# SERV.net
KiCad netlist of a schematic drawn in EAGLE
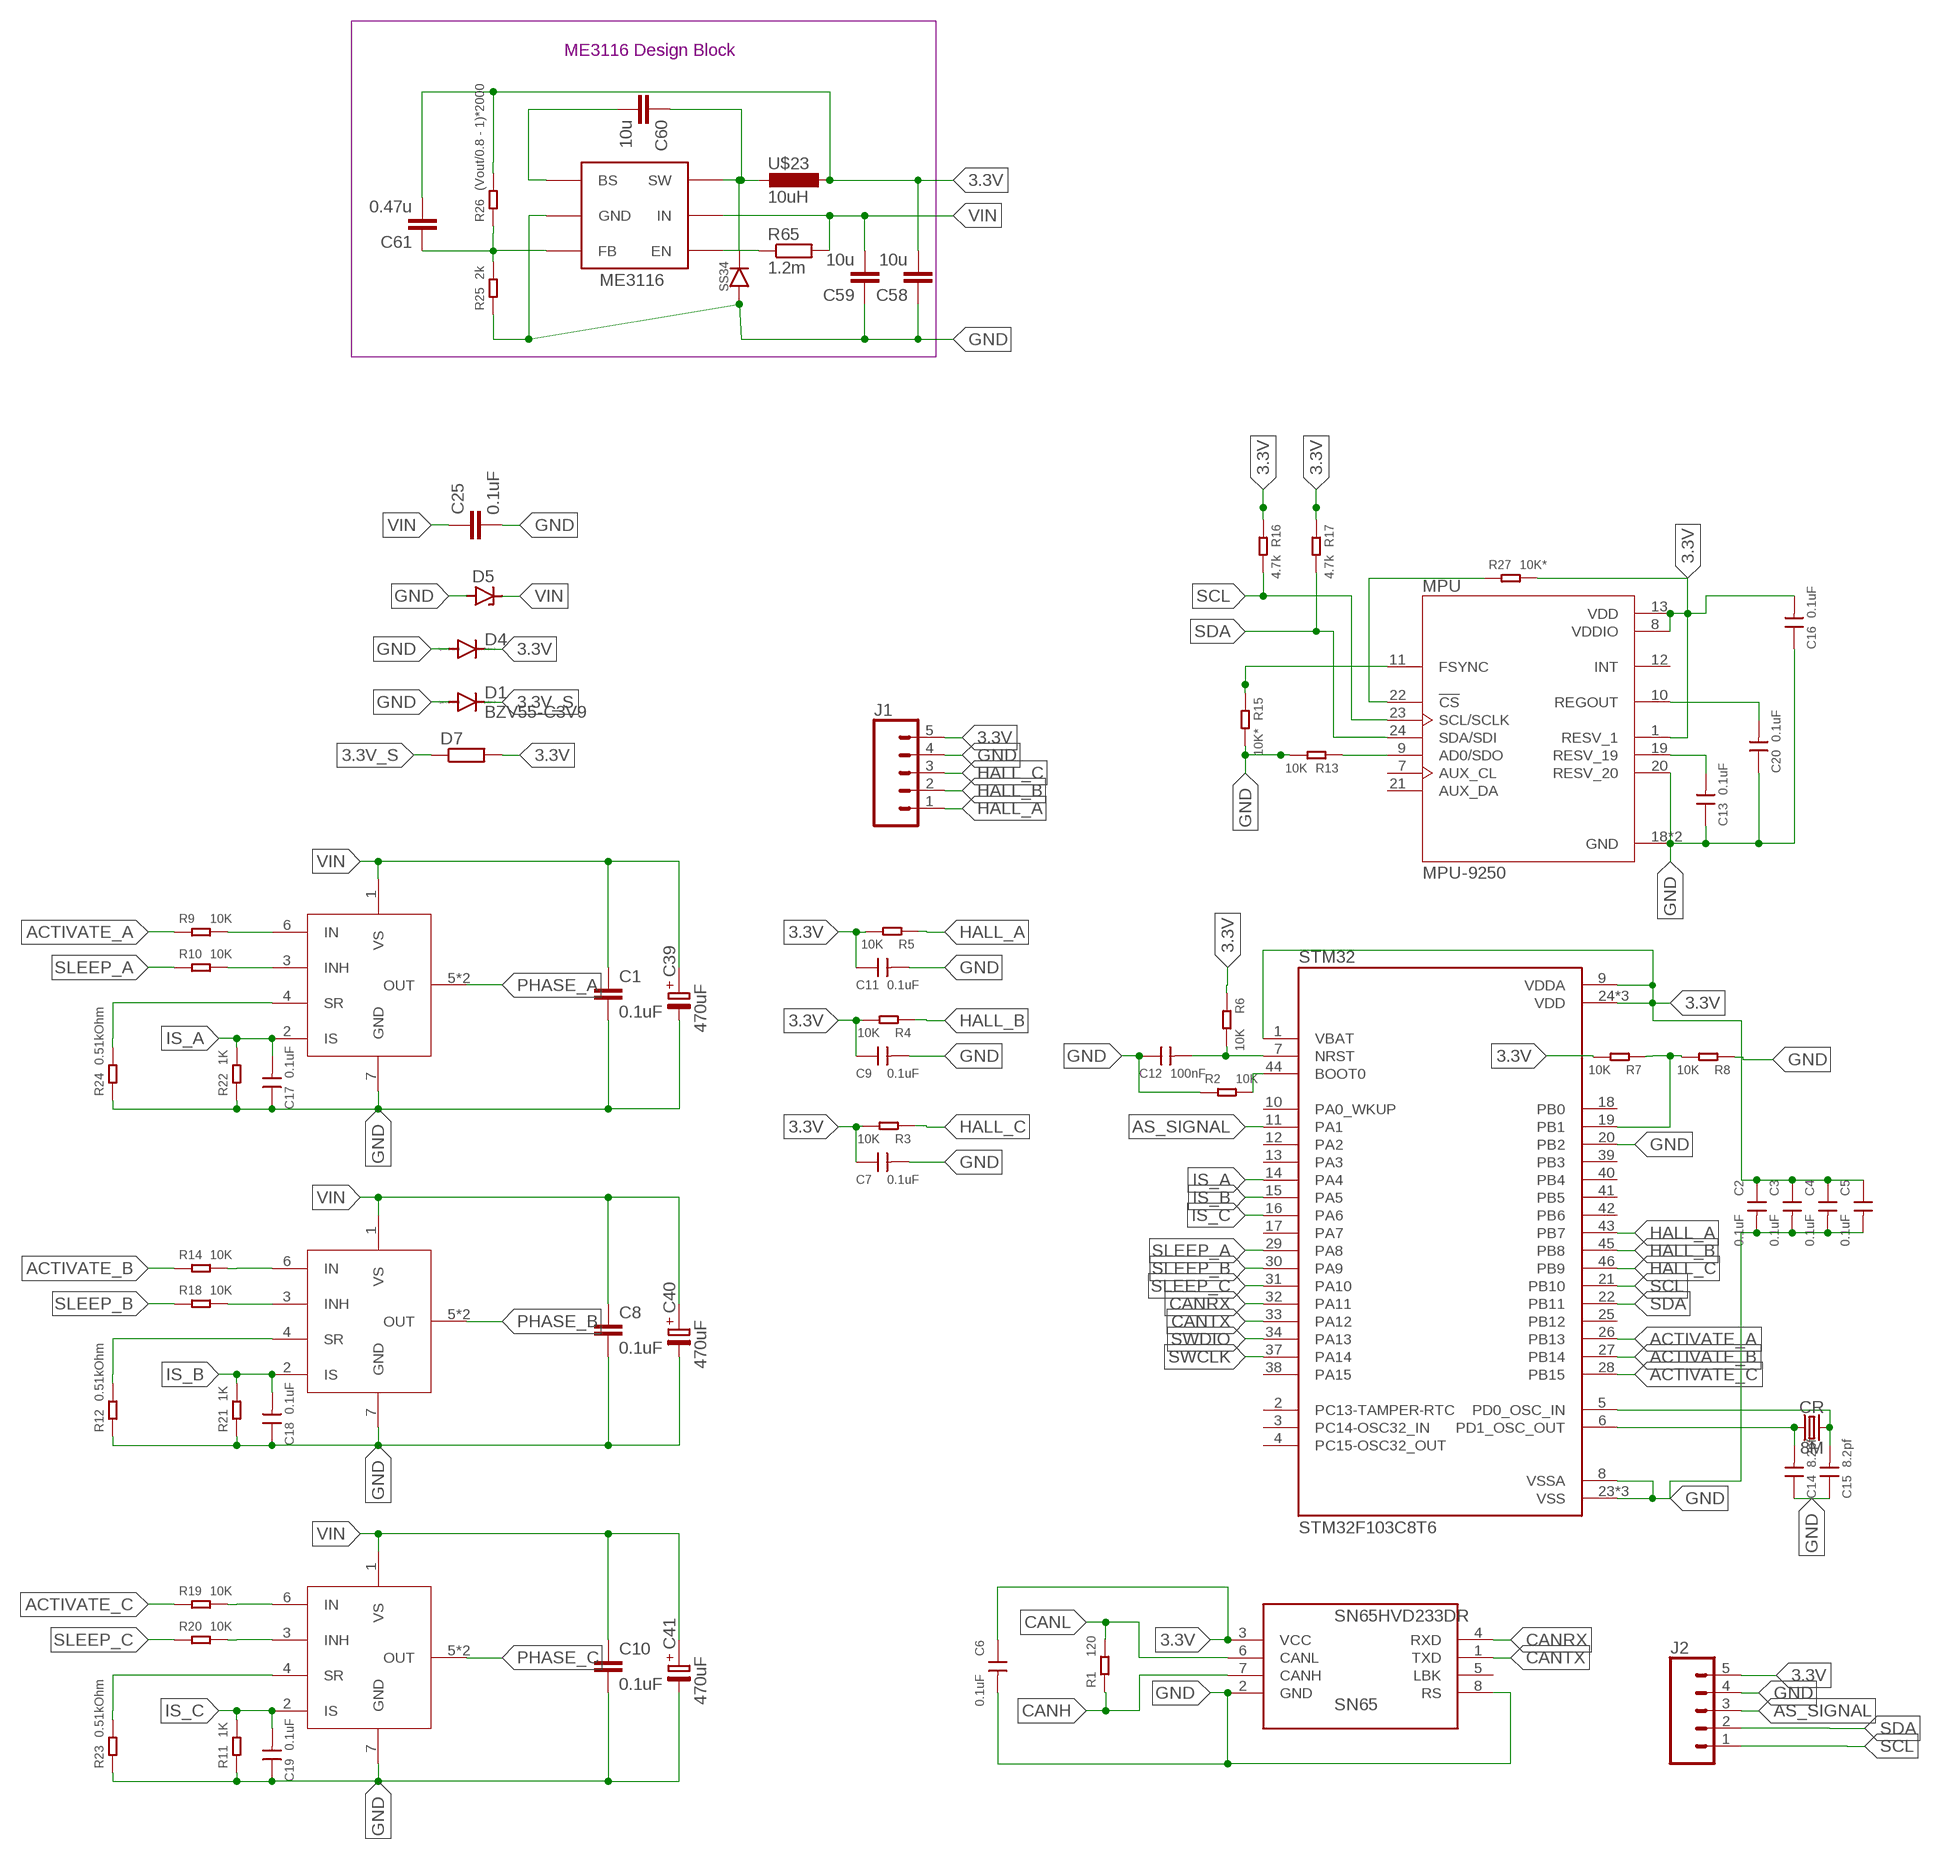
[diagram p0: schematic, sheet 1]

(export (version "E")
  (design (tool "Eeschema 10.0.6"))
  (components
    (comp (ref "BTN_A")
      (value "BTN7960B")
      (footprint "eagle-import:DPAK127P1500X440-8N")
      (libsource (lib "eagle-import") (part "BTN7960B"))
    )
    (comp (ref "BTN_B")
      (value "BTN7960B")
      (footprint "eagle-import:DPAK127P1500X440-8N")
      (libsource (lib "eagle-import") (part "BTN7960B"))
    )
    (comp (ref "BTN_C")
      (value "BTN7960B")
      (footprint "eagle-import:DPAK127P1500X440-8N")
      (libsource (lib "eagle-import") (part "BTN7960B"))
    )
    (comp (ref "C1")
      (value "0.1uF")
      (footprint "eagle-import:C1206")
      (libsource (lib "eagle-import") (part "C-EUC1206"))
    )
    (comp (ref "C2")
      (value "0.1uF")
      (footprint "eagle-import:0603")
      (libsource (lib "eagle-import") (part "C-0603"))
    )
    (comp (ref "C3")
      (value "0.1uF")
      (footprint "eagle-import:0603")
      (libsource (lib "eagle-import") (part "C-0603"))
    )
    (comp (ref "C4")
      (value "0.1uF")
      (footprint "eagle-import:0603")
      (libsource (lib "eagle-import") (part "C-0603"))
    )
    (comp (ref "C5")
      (value "0.1uF")
      (footprint "eagle-import:0603")
      (libsource (lib "eagle-import") (part "C-0603"))
    )
    (comp (ref "C6")
      (value "0.1uF")
      (footprint "eagle-import:0603")
      (libsource (lib "eagle-import") (part "C-0603"))
    )
    (comp (ref "C7")
      (value "0.1uF")
      (footprint "eagle-import:0603")
      (libsource (lib "eagle-import") (part "C-0603"))
    )
    (comp (ref "C8")
      (value "0.1uF")
      (footprint "eagle-import:C1206")
      (libsource (lib "eagle-import") (part "C-EUC1206"))
    )
    (comp (ref "C9")
      (value "0.1uF")
      (footprint "eagle-import:0603")
      (libsource (lib "eagle-import") (part "C-0603"))
    )
    (comp (ref "C10")
      (value "0.1uF")
      (footprint "eagle-import:C1206")
      (libsource (lib "eagle-import") (part "C-EUC1206"))
    )
    (comp (ref "C11")
      (value "0.1uF")
      (footprint "eagle-import:0603")
      (libsource (lib "eagle-import") (part "C-0603"))
    )
    (comp (ref "C12")
      (value "100nF")
      (footprint "eagle-import:0603")
      (libsource (lib "eagle-import") (part "C-0603"))
    )
    (comp (ref "C13")
      (value "0.1uF")
      (footprint "eagle-import:0603")
      (libsource (lib "eagle-import") (part "C-0603"))
    )
    (comp (ref "C14")
      (value "8.2pf")
      (footprint "eagle-import:0603")
      (libsource (lib "eagle-import") (part "C-0603"))
    )
    (comp (ref "C15")
      (value "8.2pf")
      (footprint "eagle-import:0603")
      (libsource (lib "eagle-import") (part "C-0603"))
    )
    (comp (ref "C16")
      (value "0.1uF")
      (footprint "eagle-import:0603")
      (libsource (lib "eagle-import") (part "C-0603"))
    )
    (comp (ref "C17")
      (value "0.1uF")
      (footprint "eagle-import:0603")
      (libsource (lib "eagle-import") (part "C-0603"))
    )
    (comp (ref "C18")
      (value "0.1uF")
      (footprint "eagle-import:0603")
      (libsource (lib "eagle-import") (part "C-0603"))
    )
    (comp (ref "C19")
      (value "0.1uF")
      (footprint "eagle-import:0603")
      (libsource (lib "eagle-import") (part "C-0603"))
    )
    (comp (ref "C20")
      (value "0.1uF")
      (footprint "eagle-import:0603")
      (libsource (lib "eagle-import") (part "C-0603"))
    )
    (comp (ref "C25")
      (value "0.1uF")
      (footprint "eagle-import:C1206")
      (libsource (lib "eagle-import") (part "C-EUC1206"))
    )
    (comp (ref "C39")
      (value "470uF")
      (footprint "eagle-import:TE-D-7343")
      (libsource (lib "eagle-import") (part "C-PR-SMD-TE-D"))
    )
    (comp (ref "C40")
      (value "470uF")
      (footprint "eagle-import:TE-D-7343")
      (libsource (lib "eagle-import") (part "C-PR-SMD-TE-D"))
    )
    (comp (ref "C41")
      (value "470uF")
      (footprint "eagle-import:TE-D-7343")
      (libsource (lib "eagle-import") (part "C-PR-SMD-TE-D"))
    )
    (comp (ref "C58")
      (value "10u")
      (footprint "eagle-import:C0805")
      (libsource (lib "eagle-import") (part "C-EUC0805"))
    )
    (comp (ref "C59")
      (value "10u")
      (footprint "eagle-import:C0805")
      (libsource (lib "eagle-import") (part "C-EUC0805"))
    )
    (comp (ref "C60")
      (value "10u")
      (footprint "eagle-import:C0805")
      (libsource (lib "eagle-import") (part "C-EUC0805"))
    )
    (comp (ref "C61")
      (value "0.47u")
      (footprint "eagle-import:C0805")
      (libsource (lib "eagle-import") (part "C-EUC0805"))
    )
    (comp (ref "CR")
      (value "8M")
      (footprint "eagle-import:CRYSTAL-SMD-3.2X2.5MM")
      (libsource (lib "eagle-import") (part "CRYSTALSMD-3.2X2.5"))
    )
    (comp (ref "D1")
      (value "BZV55-C3V9")
      (footprint "eagle-import:MINIMELF")
      (libsource (lib "eagle-import") (part "DIODE-MINIMELF"))
    )
    (comp (ref "D4")
      (value "DIODE-MINIMELF")
      (footprint "eagle-import:MINIMELF")
      (libsource (lib "eagle-import") (part "DIODE-MINIMELF"))
    )
    (comp (ref "D5")
      (value "ZENER-DIODESMB")
      (footprint "eagle-import:SMB")
      (libsource (lib "eagle-import") (part "ZENER-DIODESMB"))
    )
    (comp (ref "D7")
      (value "R-EU_R0805W")
      (footprint "eagle-import:R0805W")
      (libsource (lib "eagle-import") (part "R-EU_R0805W"))
    )
    (comp (ref "J1")
      (value "CONN_05")
      (footprint "eagle-import:1X05")
      (libsource (lib "eagle-import") (part "CONN_05"))
    )
    (comp (ref "J2")
      (value "CONN_05")
      (footprint "eagle-import:1X05")
      (libsource (lib "eagle-import") (part "CONN_05"))
    )
    (comp (ref "ME311")
      (value "ME3116")
      (footprint "eagle-import:SOT-23-6")
      (libsource (lib "eagle-import") (part "ME3116"))
    )
    (comp (ref "MPU")
      (value "MPU-9250")
      (footprint "eagle-import:QFN40P300X300X105-24N")
      (fields (field (name "MF") "TDK InvenSense"))
      (libsource (lib "eagle-import") (part "MPU-9250"))
    )
    (comp (ref "R1")
      (value "120")
      (footprint "eagle-import:0603")
      (libsource (lib "eagle-import") (part "R-0603"))
    )
    (comp (ref "R2")
      (value "10K")
      (footprint "eagle-import:0603")
      (libsource (lib "eagle-import") (part "R-0603"))
    )
    (comp (ref "R3")
      (value "10K")
      (footprint "eagle-import:0603")
      (libsource (lib "eagle-import") (part "R-0603"))
    )
    (comp (ref "R4")
      (value "10K")
      (footprint "eagle-import:0603")
      (libsource (lib "eagle-import") (part "R-0603"))
    )
    (comp (ref "R5")
      (value "10K")
      (footprint "eagle-import:0603")
      (libsource (lib "eagle-import") (part "R-0603"))
    )
    (comp (ref "R6")
      (value "10K")
      (footprint "eagle-import:0603")
      (libsource (lib "eagle-import") (part "R-0603"))
    )
    (comp (ref "R7")
      (value "10K")
      (footprint "eagle-import:0603")
      (libsource (lib "eagle-import") (part "R-0603"))
    )
    (comp (ref "R8")
      (value "10K")
      (footprint "eagle-import:0603")
      (libsource (lib "eagle-import") (part "R-0603"))
    )
    (comp (ref "R9")
      (value "10K")
      (footprint "eagle-import:0603")
      (libsource (lib "eagle-import") (part "R-0603"))
    )
    (comp (ref "R10")
      (value "10K")
      (footprint "eagle-import:0603")
      (libsource (lib "eagle-import") (part "R-0603"))
    )
    (comp (ref "R11")
      (value "1K")
      (footprint "eagle-import:0603")
      (libsource (lib "eagle-import") (part "R-0603"))
    )
    (comp (ref "R12")
      (value "0.51kOhm")
      (footprint "eagle-import:0603")
      (libsource (lib "eagle-import") (part "R-0603"))
    )
    (comp (ref "R13")
      (value "10K")
      (footprint "eagle-import:0603")
      (libsource (lib "eagle-import") (part "R-0603"))
    )
    (comp (ref "R14")
      (value "10K")
      (footprint "eagle-import:0603")
      (libsource (lib "eagle-import") (part "R-0603"))
    )
    (comp (ref "R15")
      (value "10K*")
      (footprint "eagle-import:0603")
      (libsource (lib "eagle-import") (part "R-0603"))
    )
    (comp (ref "R16")
      (value "4.7k")
      (footprint "eagle-import:0603")
      (libsource (lib "eagle-import") (part "R-0603"))
    )
    (comp (ref "R17")
      (value "4.7k")
      (footprint "eagle-import:0603")
      (libsource (lib "eagle-import") (part "R-0603"))
    )
    (comp (ref "R18")
      (value "10K")
      (footprint "eagle-import:0603")
      (libsource (lib "eagle-import") (part "R-0603"))
    )
    (comp (ref "R19")
      (value "10K")
      (footprint "eagle-import:0603")
      (libsource (lib "eagle-import") (part "R-0603"))
    )
    (comp (ref "R20")
      (value "10K")
      (footprint "eagle-import:0603")
      (libsource (lib "eagle-import") (part "R-0603"))
    )
    (comp (ref "R21")
      (value "1K")
      (footprint "eagle-import:0603")
      (libsource (lib "eagle-import") (part "R-0603"))
    )
    (comp (ref "R22")
      (value "1K")
      (footprint "eagle-import:0603")
      (libsource (lib "eagle-import") (part "R-0603"))
    )
    (comp (ref "R23")
      (value "0.51kOhm")
      (footprint "eagle-import:0603")
      (libsource (lib "eagle-import") (part "R-0603"))
    )
    (comp (ref "R24")
      (value "0.51kOhm")
      (footprint "eagle-import:0603")
      (libsource (lib "eagle-import") (part "R-0603"))
    )
    (comp (ref "R25")
      (value "2k")
      (footprint "eagle-import:0603")
      (libsource (lib "eagle-import") (part "R-0603"))
    )
    (comp (ref "R26")
      (value "(Vout/0.8 - 1)*2000")
      (footprint "eagle-import:0603")
      (libsource (lib "eagle-import") (part "R-0603"))
    )
    (comp (ref "R27")
      (value "10K*")
      (footprint "eagle-import:0603")
      (libsource (lib "eagle-import") (part "R-0603"))
    )
    (comp (ref "R65")
      (value "1.2m")
      (footprint "eagle-import:R0603")
      (libsource (lib "eagle-import") (part "R-EU_R0603"))
    )
    (comp (ref "SN65")
      (value "SN65HVD233DR")
      (footprint "eagle-import:SOIC8")
      (fields (field (name "MF") "Texas Instruments"))
      (libsource (lib "eagle-import") (part "SN65HVD233DR"))
    )
    (comp (ref "STM32")
      (value "STM32F103C8T6")
      (footprint "eagle-import:QFP50P900X900X160-48N")
      (fields (field (name "MF") "STMicroelectronics"))
      (libsource (lib "eagle-import") (part "STM32F103C8T6"))
    )
    (comp (ref "U$1")
      (value "SMA-SS34")
      (footprint "eagle-import:SMA-SS34")
      (libsource (lib "eagle-import") (part "SMA-SS34"))
    )
    (comp (ref "U$23")
      (value "10uH")
      (footprint "eagle-import:CD43")
      (libsource (lib "eagle-import") (part "INDUCTOR_CD43"))
    )
  )
  (nets
    (net (code "1") (name "3.3V") (class "Default")
      (node (ref "C11") (pin "1") (pinfunction "1_1") (pintype "passive"))
      (node (ref "C16") (pin "2") (pinfunction "2_2") (pintype "passive"))
      (node (ref "C2") (pin "1") (pinfunction "1_1") (pintype "passive"))
      (node (ref "C3") (pin "1") (pinfunction "1_1") (pintype "passive"))
      (node (ref "C4") (pin "1") (pinfunction "1_1") (pintype "passive"))
      (node (ref "C5") (pin "1") (pinfunction "1_1") (pintype "passive"))
      (node (ref "C58") (pin "2") (pinfunction "2_2") (pintype "passive"))
      (node (ref "C6") (pin "1") (pinfunction "1_1") (pintype "passive"))
      (node (ref "C61") (pin "2") (pinfunction "2_2") (pintype "passive"))
      (node (ref "C7") (pin "1") (pinfunction "1_1") (pintype "passive"))
      (node (ref "C9") (pin "1") (pinfunction "1_1") (pintype "passive"))
      (node (ref "D4") (pin "C") (pinfunction "C_C") (pintype "passive"))
      (node (ref "D7") (pin "2") (pinfunction "2_2") (pintype "passive"))
      (node (ref "J1") (pin "5") (pinfunction "5_5") (pintype "passive"))
      (node (ref "J2") (pin "5") (pinfunction "5_5") (pintype "passive"))
      (node (ref "MPU") (pin "1") (pinfunction "RESV_1_1") (pintype "passive"))
      (node (ref "MPU") (pin "13") (pinfunction "VDD_13") (pintype "power_in"))
      (node (ref "MPU") (pin "8") (pinfunction "VDDIO_8") (pintype "power_in"))
      (node (ref "R16") (pin "1") (pinfunction "1_1") (pintype "passive"))
      (node (ref "R17") (pin "1") (pinfunction "1_1") (pintype "passive"))
      (node (ref "R26") (pin "2") (pinfunction "2_2") (pintype "passive"))
      (node (ref "R27") (pin "2") (pinfunction "2_2") (pintype "passive"))
      (node (ref "R3") (pin "2") (pinfunction "2_2") (pintype "passive"))
      (node (ref "R4") (pin "2") (pinfunction "2_2") (pintype "passive"))
      (node (ref "R5") (pin "2") (pinfunction "2_2") (pintype "passive"))
      (node (ref "R6") (pin "1") (pinfunction "1_1") (pintype "passive"))
      (node (ref "R7") (pin "2") (pinfunction "2_2") (pintype "passive"))
      (node (ref "SN65") (pin "3") (pinfunction "VCC_3") (pintype "power_in"))
      (node (ref "STM32") (pin "1") (pinfunction "VBAT_1") (pintype "bidirectional"))
      (node (ref "STM32") (pin "24") (pinfunction "VDD_24") (pintype "power_in"))
      (node (ref "STM32") (pin "36") (pinfunction "VDD_36") (pintype "power_in"))
      (node (ref "STM32") (pin "48") (pinfunction "VDD_48") (pintype "power_in"))
      (node (ref "STM32") (pin "9") (pinfunction "VDDA_9") (pintype "power_in"))
      (node (ref "U$23") (pin "P$1") (pinfunction "1_P$1") (pintype "passive"))
    )
    (net (code "2") (name "3.3V_S") (class "Default")
      (node (ref "D1") (pin "C") (pinfunction "C_C") (pintype "passive"))
      (node (ref "D7") (pin "1") (pinfunction "1_1") (pintype "passive"))
    )
    (net (code "3") (name "ACTIVATE_A") (class "Default")
      (node (ref "R9") (pin "1") (pinfunction "1_1") (pintype "passive"))
      (node (ref "STM32") (pin "26") (pinfunction "PB13_26") (pintype "bidirectional"))
    )
    (net (code "4") (name "ACTIVATE_B") (class "Default")
      (node (ref "R14") (pin "1") (pinfunction "1_1") (pintype "passive"))
      (node (ref "STM32") (pin "27") (pinfunction "PB14_27") (pintype "bidirectional"))
    )
    (net (code "5") (name "ACTIVATE_C") (class "Default")
      (node (ref "R19") (pin "1") (pinfunction "1_1") (pintype "passive"))
      (node (ref "STM32") (pin "28") (pinfunction "PB15_28") (pintype "bidirectional"))
    )
    (net (code "6") (name "AS_SIGNAL") (class "Default")
      (node (ref "J2") (pin "3") (pinfunction "3_3") (pintype "passive"))
      (node (ref "STM32") (pin "11") (pinfunction "PA1_11") (pintype "bidirectional"))
    )
    (net (code "7") (name "CANH") (class "Default")
      (node (ref "R1") (pin "1") (pinfunction "1_1") (pintype "passive"))
      (node (ref "SN65") (pin "7") (pinfunction "CANH_7") (pintype "bidirectional"))
    )
    (net (code "8") (name "CANL") (class "Default")
      (node (ref "R1") (pin "2") (pinfunction "2_2") (pintype "passive"))
      (node (ref "SN65") (pin "6") (pinfunction "CANL_6") (pintype "bidirectional"))
    )
    (net (code "9") (name "CANRX") (class "Default")
      (node (ref "SN65") (pin "4") (pinfunction "RXD_4") (pintype "output"))
      (node (ref "STM32") (pin "32") (pinfunction "PA11_32") (pintype "bidirectional"))
    )
    (net (code "10") (name "CANTX") (class "Default")
      (node (ref "SN65") (pin "1") (pinfunction "TXD_1") (pintype "bidirectional"))
      (node (ref "STM32") (pin "33") (pinfunction "PA12_33") (pintype "bidirectional"))
    )
    (net (code "11") (name "GND") (class "Default")
      (node (ref "BTN_A") (pin "7") (pinfunction "GND_7") (pintype "bidirectional"))
      (node (ref "BTN_B") (pin "7") (pinfunction "GND_7") (pintype "bidirectional"))
      (node (ref "BTN_C") (pin "7") (pinfunction "GND_7") (pintype "bidirectional"))
      (node (ref "C1") (pin "2") (pinfunction "2_2") (pintype "passive"))
      (node (ref "C10") (pin "2") (pinfunction "2_2") (pintype "passive"))
      (node (ref "C11") (pin "2") (pinfunction "2_2") (pintype "passive"))
      (node (ref "C12") (pin "1") (pinfunction "1_1") (pintype "passive"))
      (node (ref "C13") (pin "1") (pinfunction "1_1") (pintype "passive"))
      (node (ref "C14") (pin "1") (pinfunction "1_1") (pintype "passive"))
      (node (ref "C15") (pin "1") (pinfunction "1_1") (pintype "passive"))
      (node (ref "C16") (pin "1") (pinfunction "1_1") (pintype "passive"))
      (node (ref "C17") (pin "1") (pinfunction "1_1") (pintype "passive"))
      (node (ref "C18") (pin "1") (pinfunction "1_1") (pintype "passive"))
      (node (ref "C19") (pin "1") (pinfunction "1_1") (pintype "passive"))
      (node (ref "C2") (pin "2") (pinfunction "2_2") (pintype "passive"))
      (node (ref "C20") (pin "1") (pinfunction "1_1") (pintype "passive"))
      (node (ref "C25") (pin "2") (pinfunction "2_2") (pintype "passive"))
      (node (ref "C3") (pin "2") (pinfunction "2_2") (pintype "passive"))
      (node (ref "C39") (pin "-") (pinfunction "-_-") (pintype "passive"))
      (node (ref "C4") (pin "2") (pinfunction "2_2") (pintype "passive"))
      (node (ref "C40") (pin "-") (pinfunction "-_-") (pintype "passive"))
      (node (ref "C41") (pin "-") (pinfunction "-_-") (pintype "passive"))
      (node (ref "C5") (pin "2") (pinfunction "2_2") (pintype "passive"))
      (node (ref "C58") (pin "1") (pinfunction "1_1") (pintype "passive"))
      (node (ref "C59") (pin "1") (pinfunction "1_1") (pintype "passive"))
      (node (ref "C6") (pin "2") (pinfunction "2_2") (pintype "passive"))
      (node (ref "C7") (pin "2") (pinfunction "2_2") (pintype "passive"))
      (node (ref "C8") (pin "2") (pinfunction "2_2") (pintype "passive"))
      (node (ref "C9") (pin "2") (pinfunction "2_2") (pintype "passive"))
      (node (ref "D1") (pin "A") (pinfunction "A_A") (pintype "passive"))
      (node (ref "D4") (pin "A") (pinfunction "A_A") (pintype "passive"))
      (node (ref "D5") (pin "A") (pinfunction "A_A") (pintype "passive"))
      (node (ref "J1") (pin "4") (pinfunction "4_4") (pintype "passive"))
      (node (ref "J2") (pin "4") (pinfunction "4_4") (pintype "passive"))
      (node (ref "ME311") (pin "2") (pinfunction "GND_2") (pintype "bidirectional"))
      (node (ref "MPU") (pin "18") (pinfunction "GND_18") (pintype "power_in"))
      (node (ref "MPU") (pin "20") (pinfunction "RESV_20_20") (pintype "passive"))
      (node (ref "MPU") (pin "25") (pinfunction "GND_25") (pintype "power_in"))
      (node (ref "R11") (pin "1") (pinfunction "1_1") (pintype "passive"))
      (node (ref "R12") (pin "1") (pinfunction "1_1") (pintype "passive"))
      (node (ref "R13") (pin "2") (pinfunction "2_2") (pintype "passive"))
      (node (ref "R15") (pin "2") (pinfunction "2_2") (pintype "passive"))
      (node (ref "R2") (pin "1") (pinfunction "1_1") (pintype "passive"))
      (node (ref "R21") (pin "1") (pinfunction "1_1") (pintype "passive"))
      (node (ref "R22") (pin "1") (pinfunction "1_1") (pintype "passive"))
      (node (ref "R23") (pin "1") (pinfunction "1_1") (pintype "passive"))
      (node (ref "R24") (pin "1") (pinfunction "1_1") (pintype "passive"))
      (node (ref "R25") (pin "1") (pinfunction "1_1") (pintype "passive"))
      (node (ref "R8") (pin "1") (pinfunction "1_1") (pintype "passive"))
      (node (ref "SN65") (pin "2") (pinfunction "GND_2") (pintype "power_in"))
      (node (ref "SN65") (pin "8") (pinfunction "RS_8") (pintype "input"))
      (node (ref "STM32") (pin "20") (pinfunction "PB2_20") (pintype "bidirectional"))
      (node (ref "STM32") (pin "23") (pinfunction "VSS_23") (pintype "power_in"))
      (node (ref "STM32") (pin "35") (pinfunction "VSS_35") (pintype "power_in"))
      (node (ref "STM32") (pin "47") (pinfunction "VSS_47") (pintype "power_in"))
      (node (ref "STM32") (pin "8") (pinfunction "VSSA_8") (pintype "power_in"))
      (node (ref "U$1") (pin "1") (pinfunction "IN_1") (pintype "input"))
    )
    (net (code "12") (name "HALL_A") (class "Default")
      (node (ref "J1") (pin "1") (pinfunction "1_1") (pintype "passive"))
      (node (ref "R5") (pin "1") (pinfunction "1_1") (pintype "passive"))
      (node (ref "STM32") (pin "43") (pinfunction "PB7_43") (pintype "bidirectional"))
    )
    (net (code "13") (name "HALL_B") (class "Default")
      (node (ref "J1") (pin "2") (pinfunction "2_2") (pintype "passive"))
      (node (ref "R4") (pin "1") (pinfunction "1_1") (pintype "passive"))
      (node (ref "STM32") (pin "45") (pinfunction "PB8_45") (pintype "bidirectional"))
    )
    (net (code "14") (name "HALL_C") (class "Default")
      (node (ref "J1") (pin "3") (pinfunction "3_3") (pintype "passive"))
      (node (ref "R3") (pin "1") (pinfunction "1_1") (pintype "passive"))
      (node (ref "STM32") (pin "46") (pinfunction "PB9_46") (pintype "bidirectional"))
    )
    (net (code "15") (name "IS_A") (class "Default")
      (node (ref "BTN_C") (pin "2") (pinfunction "IS_2") (pintype "bidirectional"))
      (node (ref "C17") (pin "2") (pinfunction "2_2") (pintype "passive"))
      (node (ref "R22") (pin "2") (pinfunction "2_2") (pintype "passive"))
      (node (ref "STM32") (pin "14") (pinfunction "PA4_14") (pintype "bidirectional"))
    )
    (net (code "16") (name "IS_B") (class "Default")
      (node (ref "BTN_B") (pin "2") (pinfunction "IS_2") (pintype "bidirectional"))
      (node (ref "C18") (pin "2") (pinfunction "2_2") (pintype "passive"))
      (node (ref "R21") (pin "2") (pinfunction "2_2") (pintype "passive"))
      (node (ref "STM32") (pin "15") (pinfunction "PA5_15") (pintype "bidirectional"))
    )
    (net (code "17") (name "IS_C") (class "Default")
      (node (ref "BTN_A") (pin "2") (pinfunction "IS_2") (pintype "bidirectional"))
      (node (ref "C19") (pin "2") (pinfunction "2_2") (pintype "passive"))
      (node (ref "R11") (pin "2") (pinfunction "2_2") (pintype "passive"))
      (node (ref "STM32") (pin "16") (pinfunction "PA6_16") (pintype "bidirectional"))
    )
    (net (code "18") (name "Net-(BTN_A-IN)") (class "Default")
      (node (ref "BTN_A") (pin "6") (pinfunction "IN_6") (pintype "bidirectional"))
      (node (ref "R19") (pin "2") (pinfunction "2_2") (pintype "passive"))
    )
    (net (code "19") (name "Net-(BTN_A-INH)") (class "Default")
      (node (ref "BTN_A") (pin "3") (pinfunction "INH_3") (pintype "bidirectional"))
      (node (ref "R20") (pin "2") (pinfunction "2_2") (pintype "passive"))
    )
    (net (code "20") (name "Net-(BTN_A-SR)") (class "Default")
      (node (ref "BTN_A") (pin "4") (pinfunction "SR_4") (pintype "bidirectional"))
      (node (ref "R23") (pin "2") (pinfunction "2_2") (pintype "passive"))
    )
    (net (code "21") (name "Net-(BTN_B-IN)") (class "Default")
      (node (ref "BTN_B") (pin "6") (pinfunction "IN_6") (pintype "bidirectional"))
      (node (ref "R14") (pin "2") (pinfunction "2_2") (pintype "passive"))
    )
    (net (code "22") (name "Net-(BTN_B-INH)") (class "Default")
      (node (ref "BTN_B") (pin "3") (pinfunction "INH_3") (pintype "bidirectional"))
      (node (ref "R18") (pin "2") (pinfunction "2_2") (pintype "passive"))
    )
    (net (code "23") (name "Net-(BTN_B-SR)") (class "Default")
      (node (ref "BTN_B") (pin "4") (pinfunction "SR_4") (pintype "bidirectional"))
      (node (ref "R12") (pin "2") (pinfunction "2_2") (pintype "passive"))
    )
    (net (code "24") (name "Net-(BTN_C-IN)") (class "Default")
      (node (ref "BTN_C") (pin "6") (pinfunction "IN_6") (pintype "bidirectional"))
      (node (ref "R9") (pin "2") (pinfunction "2_2") (pintype "passive"))
    )
    (net (code "25") (name "Net-(BTN_C-INH)") (class "Default")
      (node (ref "BTN_C") (pin "3") (pinfunction "INH_3") (pintype "bidirectional"))
      (node (ref "R10") (pin "2") (pinfunction "2_2") (pintype "passive"))
    )
    (net (code "26") (name "Net-(BTN_C-SR)") (class "Default")
      (node (ref "BTN_C") (pin "4") (pinfunction "SR_4") (pintype "bidirectional"))
      (node (ref "R24") (pin "2") (pinfunction "2_2") (pintype "passive"))
    )
    (net (code "27") (name "Net-(CR-2)") (class "Default")
      (node (ref "C15") (pin "2") (pinfunction "2_2") (pintype "passive"))
      (node (ref "CR") (pin "3") (pinfunction "2_3") (pintype "passive"))
      (node (ref "STM32") (pin "5") (pinfunction "PD0_OSC_IN_5") (pintype "bidirectional"))
    )
    (net (code "28") (name "Net-(ME311-BS)") (class "Default")
      (node (ref "C60") (pin "2") (pinfunction "2_2") (pintype "passive"))
      (node (ref "ME311") (pin "1") (pinfunction "BS_1") (pintype "bidirectional"))
    )
    (net (code "29") (name "Net-(ME311-EN)") (class "Default")
      (node (ref "ME311") (pin "4") (pinfunction "EN_4") (pintype "bidirectional"))
      (node (ref "R65") (pin "1") (pinfunction "1_1") (pintype "passive"))
    )
    (net (code "30") (name "Net-(ME311-FB)") (class "Default")
      (node (ref "C61") (pin "1") (pinfunction "1_1") (pintype "passive"))
      (node (ref "ME311") (pin "3") (pinfunction "FB_3") (pintype "bidirectional"))
      (node (ref "R25") (pin "2") (pinfunction "2_2") (pintype "passive"))
      (node (ref "R26") (pin "1") (pinfunction "1_1") (pintype "passive"))
    )
    (net (code "31") (name "Net-(ME311-SW)") (class "Default")
      (node (ref "C60") (pin "1") (pinfunction "1_1") (pintype "passive"))
      (node (ref "ME311") (pin "6") (pinfunction "SW_6") (pintype "bidirectional"))
      (node (ref "U$1") (pin "2") (pinfunction "OUT_2") (pintype "bidirectional"))
      (node (ref "U$23") (pin "P$2") (pinfunction "2_P$2") (pintype "passive"))
    )
    (net (code "32") (name "Net-(MPU-AD0{slash}SDO)") (class "Default")
      (node (ref "MPU") (pin "9") (pinfunction "AD0/SDO_9") (pintype "output"))
      (node (ref "R13") (pin "1") (pinfunction "1_1") (pintype "passive"))
    )
    (net (code "33") (name "Net-(MPU-FSYNC)") (class "Default")
      (node (ref "MPU") (pin "11") (pinfunction "FSYNC_11") (pintype "input"))
      (node (ref "R15") (pin "1") (pinfunction "1_1") (pintype "passive"))
    )
    (net (code "34") (name "Net-(MPU-REGOUT)") (class "Default")
      (node (ref "C20") (pin "2") (pinfunction "2_2") (pintype "passive"))
      (node (ref "MPU") (pin "10") (pinfunction "REGOUT_10") (pintype "output"))
    )
    (net (code "35") (name "Net-(MPU-RESV_19)") (class "Default")
      (node (ref "C13") (pin "2") (pinfunction "2_2") (pintype "passive"))
      (node (ref "MPU") (pin "19") (pinfunction "RESV_19_19") (pintype "passive"))
    )
    (net (code "36") (name "Net-(MPU-~{CS})") (class "Default")
      (node (ref "MPU") (pin "22") (pinfunction "~{CS}_22") (pintype "input"))
      (node (ref "R27") (pin "1") (pinfunction "1_1") (pintype "passive"))
    )
    (net (code "37") (name "Net-(STM32-BOOT0)") (class "Default")
      (node (ref "R2") (pin "2") (pinfunction "2_2") (pintype "passive"))
      (node (ref "STM32") (pin "44") (pinfunction "BOOT0_44") (pintype "input"))
    )
    (net (code "38") (name "Net-(STM32-NRST)") (class "Default")
      (node (ref "C12") (pin "2") (pinfunction "2_2") (pintype "passive"))
      (node (ref "R6") (pin "2") (pinfunction "2_2") (pintype "passive"))
      (node (ref "STM32") (pin "7") (pinfunction "NRST_7") (pintype "input"))
    )
    (net (code "39") (name "Net-(STM32-PB1)") (class "Default")
      (node (ref "R7") (pin "1") (pinfunction "1_1") (pintype "passive"))
      (node (ref "R8") (pin "2") (pinfunction "2_2") (pintype "passive"))
      (node (ref "STM32") (pin "19") (pinfunction "PB1_19") (pintype "bidirectional"))
    )
    (net (code "40") (name "Net-(STM32-PD1_OSC_OUT)") (class "Default")
      (node (ref "C14") (pin "2") (pinfunction "2_2") (pintype "passive"))
      (node (ref "CR") (pin "1") (pinfunction "1_1") (pintype "passive"))
      (node (ref "STM32") (pin "6") (pinfunction "PD1_OSC_OUT_6") (pintype "bidirectional"))
    )
    (net (code "41") (name "PHASE_A") (class "Default")
      (node (ref "BTN_C") (pin "5") (pinfunction "OUT_5") (pintype "bidirectional"))
      (node (ref "BTN_C") (pin "8") (pinfunction "OUT_8") (pintype "bidirectional"))
    )
    (net (code "42") (name "PHASE_B") (class "Default")
      (node (ref "BTN_B") (pin "5") (pinfunction "OUT_5") (pintype "bidirectional"))
      (node (ref "BTN_B") (pin "8") (pinfunction "OUT_8") (pintype "bidirectional"))
    )
    (net (code "43") (name "PHASE_C") (class "Default")
      (node (ref "BTN_A") (pin "5") (pinfunction "OUT_5") (pintype "bidirectional"))
      (node (ref "BTN_A") (pin "8") (pinfunction "OUT_8") (pintype "bidirectional"))
    )
    (net (code "44") (name "SCL") (class "Default")
      (node (ref "J2") (pin "1") (pinfunction "1_1") (pintype "passive"))
      (node (ref "MPU") (pin "23") (pinfunction "SCL/SCLK_23") (pintype "input"))
      (node (ref "R16") (pin "2") (pinfunction "2_2") (pintype "passive"))
      (node (ref "STM32") (pin "21") (pinfunction "PB10_21") (pintype "bidirectional"))
    )
    (net (code "45") (name "SDA") (class "Default")
      (node (ref "J2") (pin "2") (pinfunction "2_2") (pintype "passive"))
      (node (ref "MPU") (pin "24") (pinfunction "SDA/SDI_24") (pintype "bidirectional"))
      (node (ref "R17") (pin "2") (pinfunction "2_2") (pintype "passive"))
      (node (ref "STM32") (pin "22") (pinfunction "PB11_22") (pintype "bidirectional"))
    )
    (net (code "46") (name "SLEEP_A") (class "Default")
      (node (ref "R10") (pin "1") (pinfunction "1_1") (pintype "passive"))
      (node (ref "STM32") (pin "29") (pinfunction "PA8_29") (pintype "bidirectional"))
    )
    (net (code "47") (name "SLEEP_B") (class "Default")
      (node (ref "R18") (pin "1") (pinfunction "1_1") (pintype "passive"))
      (node (ref "STM32") (pin "30") (pinfunction "PA9_30") (pintype "bidirectional"))
    )
    (net (code "48") (name "SLEEP_C") (class "Default")
      (node (ref "R20") (pin "1") (pinfunction "1_1") (pintype "passive"))
      (node (ref "STM32") (pin "31") (pinfunction "PA10_31") (pintype "bidirectional"))
    )
    (net (code "49") (name "SWCLK") (class "Default")
      (node (ref "STM32") (pin "37") (pinfunction "PA14_37") (pintype "bidirectional"))
    )
    (net (code "50") (name "SWDIO") (class "Default")
      (node (ref "STM32") (pin "34") (pinfunction "PA13_34") (pintype "bidirectional"))
    )
    (net (code "51") (name "VIN") (class "Default")
      (node (ref "BTN_A") (pin "1") (pinfunction "VS_1") (pintype "bidirectional"))
      (node (ref "BTN_B") (pin "1") (pinfunction "VS_1") (pintype "bidirectional"))
      (node (ref "BTN_C") (pin "1") (pinfunction "VS_1") (pintype "bidirectional"))
      (node (ref "C1") (pin "1") (pinfunction "1_1") (pintype "passive"))
      (node (ref "C10") (pin "1") (pinfunction "1_1") (pintype "passive"))
      (node (ref "C25") (pin "1") (pinfunction "1_1") (pintype "passive"))
      (node (ref "C39") (pin "+") (pinfunction "+_+") (pintype "passive"))
      (node (ref "C40") (pin "+") (pinfunction "+_+") (pintype "passive"))
      (node (ref "C41") (pin "+") (pinfunction "+_+") (pintype "passive"))
      (node (ref "C59") (pin "2") (pinfunction "2_2") (pintype "passive"))
      (node (ref "C8") (pin "1") (pinfunction "1_1") (pintype "passive"))
      (node (ref "D5") (pin "C") (pinfunction "C_C") (pintype "passive"))
      (node (ref "ME311") (pin "5") (pinfunction "IN_5") (pintype "bidirectional"))
      (node (ref "R65") (pin "2") (pinfunction "2_2") (pintype "passive"))
    )
    (net (code "52") (name "unconnected-(MPU-AUX_CL-Pad7)") (class "Default")
      (node (ref "MPU") (pin "7") (pinfunction "AUX_CL_7") (pintype "input"))
    )
    (net (code "53") (name "unconnected-(MPU-AUX_DA-Pad21)") (class "Default")
      (node (ref "MPU") (pin "21") (pinfunction "AUX_DA_21") (pintype "input"))
    )
    (net (code "54") (name "unconnected-(MPU-INT-Pad12)") (class "Default")
      (node (ref "MPU") (pin "12") (pinfunction "INT_12") (pintype "output"))
    )
    (net (code "55") (name "unconnected-(SN65-LBK-Pad5)") (class "Default")
      (node (ref "SN65") (pin "5") (pinfunction "LBK_5") (pintype "output"))
    )
    (net (code "56") (name "unconnected-(STM32-PA0_WKUP-Pad10)") (class "Default")
      (node (ref "STM32") (pin "10") (pinfunction "PA0_WKUP_10") (pintype "bidirectional"))
    )
    (net (code "57") (name "unconnected-(STM32-PA2-Pad12)") (class "Default")
      (node (ref "STM32") (pin "12") (pinfunction "PA2_12") (pintype "bidirectional"))
    )
    (net (code "58") (name "unconnected-(STM32-PA3-Pad13)") (class "Default")
      (node (ref "STM32") (pin "13") (pinfunction "PA3_13") (pintype "bidirectional"))
    )
    (net (code "59") (name "unconnected-(STM32-PA7-Pad17)") (class "Default")
      (node (ref "STM32") (pin "17") (pinfunction "PA7_17") (pintype "bidirectional"))
    )
    (net (code "60") (name "unconnected-(STM32-PA15-Pad38)") (class "Default")
      (node (ref "STM32") (pin "38") (pinfunction "PA15_38") (pintype "bidirectional"))
    )
    (net (code "61") (name "unconnected-(STM32-PB0-Pad18)") (class "Default")
      (node (ref "STM32") (pin "18") (pinfunction "PB0_18") (pintype "bidirectional"))
    )
    (net (code "62") (name "unconnected-(STM32-PB3-Pad39)") (class "Default")
      (node (ref "STM32") (pin "39") (pinfunction "PB3_39") (pintype "bidirectional"))
    )
    (net (code "63") (name "unconnected-(STM32-PB4-Pad40)") (class "Default")
      (node (ref "STM32") (pin "40") (pinfunction "PB4_40") (pintype "bidirectional"))
    )
    (net (code "64") (name "unconnected-(STM32-PB5-Pad41)") (class "Default")
      (node (ref "STM32") (pin "41") (pinfunction "PB5_41") (pintype "bidirectional"))
    )
    (net (code "65") (name "unconnected-(STM32-PB6-Pad42)") (class "Default")
      (node (ref "STM32") (pin "42") (pinfunction "PB6_42") (pintype "bidirectional"))
    )
    (net (code "66") (name "unconnected-(STM32-PB12-Pad25)") (class "Default")
      (node (ref "STM32") (pin "25") (pinfunction "PB12_25") (pintype "bidirectional"))
    )
    (net (code "67") (name "unconnected-(STM32-PC13-TAMPER-RTC-Pad2)") (class "Default")
      (node (ref "STM32") (pin "2") (pinfunction "PC13-TAMPER-RTC_2") (pintype "bidirectional"))
    )
    (net (code "68") (name "unconnected-(STM32-PC14-OSC32_IN-Pad3)") (class "Default")
      (node (ref "STM32") (pin "3") (pinfunction "PC14-OSC32_IN_3") (pintype "bidirectional"))
    )
    (net (code "69") (name "unconnected-(STM32-PC15-OSC32_OUT-Pad4)") (class "Default")
      (node (ref "STM32") (pin "4") (pinfunction "PC15-OSC32_OUT_4") (pintype "bidirectional"))
    )
  )
)
